# MSP430.net
KiCad netlist of a schematic drawn in Altium Designer
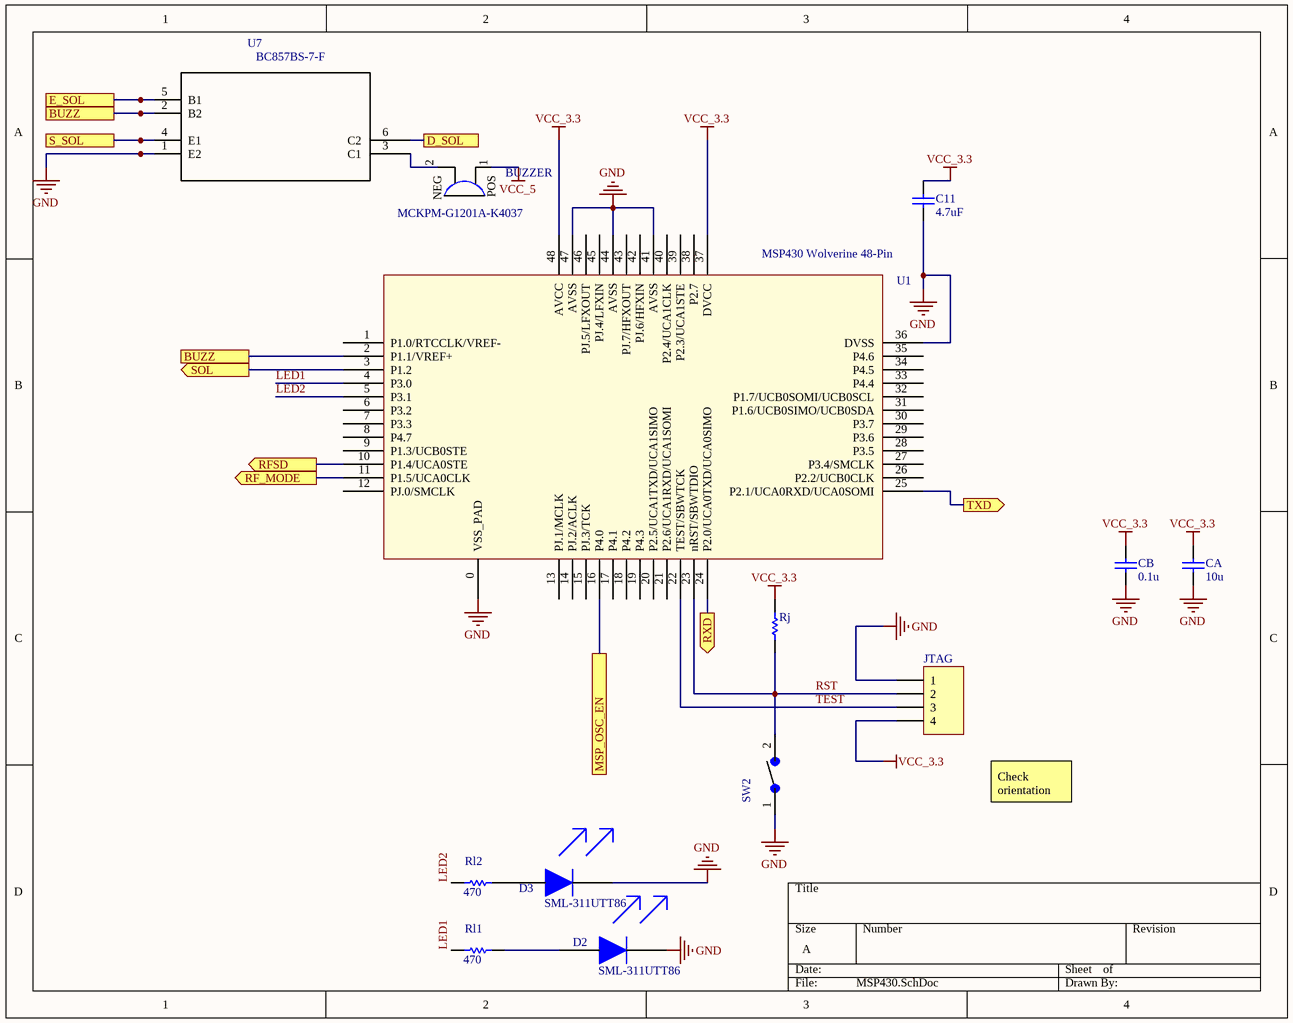
[diagram p0: MSP430.SchDoc]

(export (version "E")
  (design (tool "Eeschema 10.0.6"))
  (components
    (comp (ref "BUZZER")
      (value "MCKPM-G1201A-K4037")
      (footprint "XDCR_MCKPM-G1201A-K4037")
      (description "Magnetic Buzzer And Transducer")
      (fields (field (name "MF") "Multicomp"))
      (libsource (lib "MCKPM-G1201A-K4037") (part "MCKPM-G1201A-K4037"))
    )
    (comp (ref "C11")
      (value "4.7uF")
      (footprint "0402-W")
      (description "Ceramic Capacitor (Surface Mount)")
      (fields (field (name "MANUFACTURER") "Generic Ceramic Chip Cap (TBD)") (field (name "Comment") "Cap"))
      (libsource (lib "WISP_AD10") (part "Cap"))
    )
    (comp (ref "CA")
      (value "10u")
      (footprint "0402-W")
      (description "Ceramic Capacitor (Surface Mount)")
      (fields (field (name "MANUFACTURER") "Generic Ceramic Chip Cap (TBD)") (field (name "Comment") "Cap"))
      (libsource (lib "wisp") (part "Cap"))
    )
    (comp (ref "CB")
      (value "0.1u")
      (footprint "0402-W")
      (description "Ceramic Capacitor (Surface Mount)")
      (fields (field (name "MANUFACTURER") "Generic Ceramic Chip Cap (TBD)") (field (name "Comment") "Cap"))
      (libsource (lib "wisp") (part "Cap"))
    )
    (comp (ref "D2")
      (value "SML-311UTT86")
      (footprint "0603")
      (description "LED 630NM RED WTR CLR 0603 SMD")
      (libsource (lib "Fromm") (part "SML-311UTT86"))
    )
    (comp (ref "D3")
      (value "SML-311UTT86")
      (footprint "0603")
      (description "LED 630NM RED WTR CLR 0603 SMD")
      (libsource (lib "Fromm") (part "SML-311UTT86"))
    )
    (comp (ref "JTAG")
      (value "MHDR1X4")
      (footprint "MHDR1X4")
      (description "Header, 4-Pin")
      (fields (field (name "PUBLISHER") "Altium Limited"))
      (libsource (lib "Miscellaneous Connectors") (part "MHDR1X4"))
    )
    (comp (ref "Rj")
      (value "Res")
      (footprint "0402")
      (description "Chip Resistor (Surface Mount)")
      (fields (field (name "MANUFACTURER") "Generic Chip Res (TBD)"))
      (libsource (lib "WISP_AD10") (part "Res"))
    )
    (comp (ref "Rl1")
      (value "470")
      (footprint "0402")
      (description "Chip Resistor (Surface Mount)")
      (fields (field (name "MANUFACTURER") "Generic Chip Res (TBD)") (field (name "Comment") "Res"))
      (libsource (lib "wisp") (part "Res"))
    )
    (comp (ref "Rl2")
      (value "470")
      (footprint "0402")
      (description "Chip Resistor (Surface Mount)")
      (fields (field (name "MANUFACTURER") "Generic Chip Res (TBD)") (field (name "Comment") "Res"))
      (libsource (lib "wisp") (part "Res"))
    )
    (comp (ref "SW2")
      (value "FSMSM _1437566-3_")
      (footprint "TE_FSMSM")
      (description "FSMSM=3.5X6 SMT TACT")
      (fields (field (name "MF") "TE Connectivity") (field (name "MP") "FSMSM"))
      (libsource (lib "FSMSM") (part "FSMSM"))
    )
    (comp (ref "U1")
      (value "MSP430 Wolverine 48-Pin")
      (footprint "MSP_QFN48_RGZ_PAD0")
      (description "16-bit FRAM MCU")
      (libsource (lib "wisp") (part "MSP430FR596X_586X_RGZ"))
    )
    (comp (ref "U7")
      (value "BC857BS-7-F")
      (footprint "SOT65P210X100-6N")
      (description "BC857BS Series PNP 45 V 200 mW Small Signal Transistor SMT - SOT-363")
      (fields (field (name "MF") "Diodes Inc."))
      (libsource (lib "BC857BS-7-F") (part "BC857BS-7-F"))
    )
  )
  (nets
    (net (code "1") (name "/BUZZ") (class "Default")
      (node (ref "U1") (pin "2") (pinfunction "P1.1/VREF+_2") (pintype "passive"))
      (node (ref "U7") (pin "2") (pinfunction "B2_2") (pintype "passive"))
    )
    (net (code "2") (name "/D_SOL") (class "Default")
      (node (ref "U7") (pin "6") (pinfunction "C2_6") (pintype "passive"))
    )
    (net (code "3") (name "/E_SOL") (class "Default")
      (node (ref "U7") (pin "5") (pinfunction "B1_5") (pintype "passive"))
    )
    (net (code "4") (name "/LED1") (class "Default")
      (node (ref "Rl1") (pin "2") (pinfunction "2_2") (pintype "passive"))
      (node (ref "U1") (pin "4") (pinfunction "P3.0_4") (pintype "passive"))
    )
    (net (code "5") (name "/LED2") (class "Default")
      (node (ref "Rl2") (pin "2") (pinfunction "2_2") (pintype "passive"))
      (node (ref "U1") (pin "5") (pinfunction "P3.1_5") (pintype "passive"))
    )
    (net (code "6") (name "/MSP_OSC_EN") (class "Default")
      (node (ref "U1") (pin "16") (pinfunction "P4.0_16") (pintype "passive"))
    )
    (net (code "7") (name "/RFSD") (class "Default")
      (node (ref "U1") (pin "10") (pinfunction "P1.4/UCA0STE_10") (pintype "passive"))
    )
    (net (code "8") (name "/RF_MODE") (class "Default")
      (node (ref "U1") (pin "11") (pinfunction "P1.5/UCA0CLK_11") (pintype "passive"))
    )
    (net (code "9") (name "/RST") (class "Default")
      (node (ref "JTAG") (pin "2") (pinfunction "2_2") (pintype "passive"))
      (node (ref "Rj") (pin "1") (pinfunction "1_1") (pintype "passive"))
      (node (ref "SW2") (pin "2") (pinfunction "2_2") (pintype "passive"))
      (node (ref "U1") (pin "23") (pinfunction "nRST/SBWTDIO_23") (pintype "passive"))
    )
    (net (code "10") (name "/RXD") (class "Default")
      (node (ref "U1") (pin "24") (pinfunction "P2.0/UCA0TXD/UCA0SIMO_24") (pintype "passive"))
    )
    (net (code "11") (name "/SOL") (class "Default")
      (node (ref "U1") (pin "3") (pinfunction "P1.2_3") (pintype "passive"))
    )
    (net (code "12") (name "/S_SOL") (class "Default")
      (node (ref "U7") (pin "4") (pinfunction "E1_4") (pintype "passive"))
    )
    (net (code "13") (name "/TEST") (class "Default")
      (node (ref "JTAG") (pin "3") (pinfunction "3_3") (pintype "passive"))
      (node (ref "U1") (pin "22") (pinfunction "TEST/SBWTCK_22") (pintype "passive"))
    )
    (net (code "14") (name "/TXD") (class "Default")
      (node (ref "U1") (pin "25") (pinfunction "P2.1/UCA0RXD/UCA0SOMI_25") (pintype "passive"))
    )
    (net (code "15") (name "GND") (class "Default")
      (node (ref "C11") (pin "1") (pinfunction "1_1") (pintype "passive"))
      (node (ref "CA") (pin "1") (pinfunction "1_1") (pintype "passive"))
      (node (ref "CB") (pin "1") (pinfunction "1_1") (pintype "passive"))
      (node (ref "D2") (pin "2") (pintype "passive"))
      (node (ref "D3") (pin "2") (pintype "passive"))
      (node (ref "JTAG") (pin "1") (pinfunction "1_1") (pintype "passive"))
      (node (ref "SW2") (pin "1") (pinfunction "1_1") (pintype "passive"))
      (node (ref "U1") (pin "0") (pinfunction "VSS_PAD_0") (pintype "passive"))
      (node (ref "U1") (pin "36") (pinfunction "DVSS_36") (pintype "passive"))
      (node (ref "U1") (pin "41") (pinfunction "AVSS_41") (pintype "passive"))
      (node (ref "U1") (pin "44") (pinfunction "AVSS_44") (pintype "passive"))
      (node (ref "U1") (pin "47") (pinfunction "AVSS_47") (pintype "passive"))
      (node (ref "U7") (pin "1") (pinfunction "E2_1") (pintype "passive"))
    )
    (net (code "16") (name "Net-(BUZZER-NEG)") (class "Default")
      (node (ref "BUZZER") (pin "2") (pinfunction "NEG_2") (pintype "passive"))
      (node (ref "U7") (pin "3") (pinfunction "C1_3") (pintype "passive"))
    )
    (net (code "17") (name "Net-(D2-Pad1)") (class "Default")
      (node (ref "D2") (pin "1") (pintype "passive"))
      (node (ref "Rl1") (pin "1") (pinfunction "1_1") (pintype "passive"))
    )
    (net (code "18") (name "Net-(D3-Pad1)") (class "Default")
      (node (ref "D3") (pin "1") (pintype "passive"))
      (node (ref "Rl2") (pin "1") (pinfunction "1_1") (pintype "passive"))
    )
    (net (code "19") (name "VCC_3.3") (class "Default")
      (node (ref "C11") (pin "2") (pinfunction "2_2") (pintype "passive"))
      (node (ref "CA") (pin "2") (pinfunction "2_2") (pintype "passive"))
      (node (ref "CB") (pin "2") (pinfunction "2_2") (pintype "passive"))
      (node (ref "JTAG") (pin "4") (pinfunction "4_4") (pintype "passive"))
      (node (ref "Rj") (pin "2") (pinfunction "2_2") (pintype "passive"))
      (node (ref "U1") (pin "37") (pinfunction "DVCC_37") (pintype "passive"))
      (node (ref "U1") (pin "48") (pinfunction "AVCC_48") (pintype "passive"))
    )
    (net (code "20") (name "VCC_5") (class "Default")
      (node (ref "BUZZER") (pin "1") (pinfunction "POS_1") (pintype "passive"))
    )
    (net (code "21") (name "unconnected-(U1-P1.0{slash}RTCCLK{slash}VREF--Pad1)") (class "Default")
      (node (ref "U1") (pin "1") (pinfunction "P1.0/RTCCLK/VREF-_1") (pintype "passive"))
    )
    (net (code "22") (name "unconnected-(U1-P1.3{slash}UCB0STE-Pad9)") (class "Default")
      (node (ref "U1") (pin "9") (pinfunction "P1.3/UCB0STE_9") (pintype "passive"))
    )
    (net (code "23") (name "unconnected-(U1-P1.6{slash}UCB0SIMO{slash}UCB0SDA-Pad31)") (class "Default")
      (node (ref "U1") (pin "31") (pinfunction "P1.6/UCB0SIMO/UCB0SDA_31") (pintype "passive"))
    )
    (net (code "24") (name "unconnected-(U1-P1.7{slash}UCB0SOMI{slash}UCB0SCL-Pad32)") (class "Default")
      (node (ref "U1") (pin "32") (pinfunction "P1.7/UCB0SOMI/UCB0SCL_32") (pintype "passive"))
    )
    (net (code "25") (name "unconnected-(U1-P2.2{slash}UCB0CLK-Pad26)") (class "Default")
      (node (ref "U1") (pin "26") (pinfunction "P2.2/UCB0CLK_26") (pintype "passive"))
    )
    (net (code "26") (name "unconnected-(U1-P2.3{slash}UCA1STE-Pad39)") (class "Default")
      (node (ref "U1") (pin "39") (pinfunction "P2.3/UCA1STE_39") (pintype "passive"))
    )
    (net (code "27") (name "unconnected-(U1-P2.4{slash}UCA1CLK-Pad40)") (class "Default")
      (node (ref "U1") (pin "40") (pinfunction "P2.4/UCA1CLK_40") (pintype "passive"))
    )
    (net (code "28") (name "unconnected-(U1-P2.5{slash}UCA1TXD{slash}UCA1SIMO-Pad20)") (class "Default")
      (node (ref "U1") (pin "20") (pinfunction "P2.5/UCA1TXD/UCA1SIMO_20") (pintype "passive"))
    )
    (net (code "29") (name "unconnected-(U1-P2.6{slash}UCA1RXD{slash}UCA1SOMI-Pad21)") (class "Default")
      (node (ref "U1") (pin "21") (pinfunction "P2.6/UCA1RXD/UCA1SOMI_21") (pintype "passive"))
    )
    (net (code "30") (name "unconnected-(U1-P2.7-Pad38)") (class "Default")
      (node (ref "U1") (pin "38") (pinfunction "P2.7_38") (pintype "passive"))
    )
    (net (code "31") (name "unconnected-(U1-P3.2-Pad6)") (class "Default")
      (node (ref "U1") (pin "6") (pinfunction "P3.2_6") (pintype "passive"))
    )
    (net (code "32") (name "unconnected-(U1-P3.3-Pad7)") (class "Default")
      (node (ref "U1") (pin "7") (pinfunction "P3.3_7") (pintype "passive"))
    )
    (net (code "33") (name "unconnected-(U1-P3.4{slash}SMCLK-Pad27)") (class "Default")
      (node (ref "U1") (pin "27") (pinfunction "P3.4/SMCLK_27") (pintype "passive"))
    )
    (net (code "34") (name "unconnected-(U1-P3.5-Pad28)") (class "Default")
      (node (ref "U1") (pin "28") (pinfunction "P3.5_28") (pintype "passive"))
    )
    (net (code "35") (name "unconnected-(U1-P3.6-Pad29)") (class "Default")
      (node (ref "U1") (pin "29") (pinfunction "P3.6_29") (pintype "passive"))
    )
    (net (code "36") (name "unconnected-(U1-P3.7-Pad30)") (class "Default")
      (node (ref "U1") (pin "30") (pinfunction "P3.7_30") (pintype "passive"))
    )
    (net (code "37") (name "unconnected-(U1-P4.1-Pad17)") (class "Default")
      (node (ref "U1") (pin "17") (pinfunction "P4.1_17") (pintype "passive"))
    )
    (net (code "38") (name "unconnected-(U1-P4.2-Pad18)") (class "Default")
      (node (ref "U1") (pin "18") (pinfunction "P4.2_18") (pintype "passive"))
    )
    (net (code "39") (name "unconnected-(U1-P4.3-Pad19)") (class "Default")
      (node (ref "U1") (pin "19") (pinfunction "P4.3_19") (pintype "passive"))
    )
    (net (code "40") (name "unconnected-(U1-P4.4-Pad33)") (class "Default")
      (node (ref "U1") (pin "33") (pinfunction "P4.4_33") (pintype "passive"))
    )
    (net (code "41") (name "unconnected-(U1-P4.5-Pad34)") (class "Default")
      (node (ref "U1") (pin "34") (pinfunction "P4.5_34") (pintype "passive"))
    )
    (net (code "42") (name "unconnected-(U1-P4.6-Pad35)") (class "Default")
      (node (ref "U1") (pin "35") (pinfunction "P4.6_35") (pintype "passive"))
    )
    (net (code "43") (name "unconnected-(U1-P4.7-Pad8)") (class "Default")
      (node (ref "U1") (pin "8") (pinfunction "P4.7_8") (pintype "passive"))
    )
    (net (code "44") (name "unconnected-(U1-PJ.0{slash}SMCLK-Pad12)") (class "Default")
      (node (ref "U1") (pin "12") (pinfunction "PJ.0/SMCLK_12") (pintype "passive"))
    )
    (net (code "45") (name "unconnected-(U1-PJ.1{slash}MCLK-Pad13)") (class "Default")
      (node (ref "U1") (pin "13") (pinfunction "PJ.1/MCLK_13") (pintype "passive"))
    )
    (net (code "46") (name "unconnected-(U1-PJ.2{slash}ACLK-Pad14)") (class "Default")
      (node (ref "U1") (pin "14") (pinfunction "PJ.2/ACLK_14") (pintype "passive"))
    )
    (net (code "47") (name "unconnected-(U1-PJ.3{slash}TCK-Pad15)") (class "Default")
      (node (ref "U1") (pin "15") (pinfunction "PJ.3/TCK_15") (pintype "passive"))
    )
    (net (code "48") (name "unconnected-(U1-PJ.4{slash}LFXIN-Pad45)") (class "Default")
      (node (ref "U1") (pin "45") (pinfunction "PJ.4/LFXIN_45") (pintype "passive"))
    )
    (net (code "49") (name "unconnected-(U1-PJ.5{slash}LFXOUT-Pad46)") (class "Default")
      (node (ref "U1") (pin "46") (pinfunction "PJ.5/LFXOUT_46") (pintype "passive"))
    )
    (net (code "50") (name "unconnected-(U1-PJ.6{slash}HFXIN-Pad42)") (class "Default")
      (node (ref "U1") (pin "42") (pinfunction "PJ.6/HFXIN_42") (pintype "passive"))
    )
    (net (code "51") (name "unconnected-(U1-PJ.7{slash}HFXOUT-Pad43)") (class "Default")
      (node (ref "U1") (pin "43") (pinfunction "PJ.7/HFXOUT_43") (pintype "passive"))
    )
  )
)
